# Ground_Station_Board.net
KiCad netlist of a schematic drawn in EAGLE
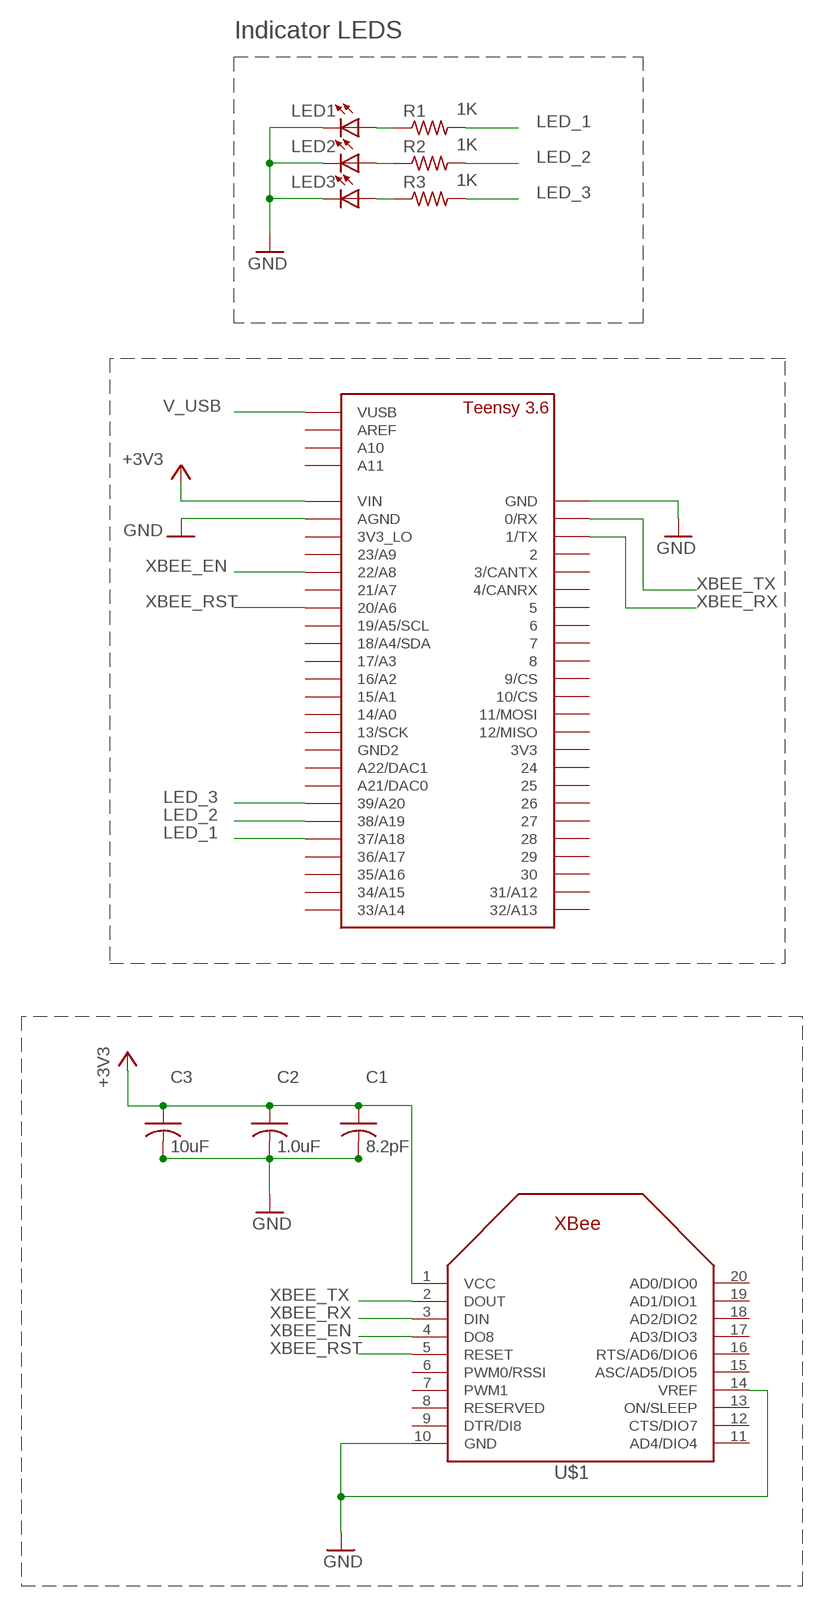
[diagram p0: schematic, sheet 1]

(export (version "E")
  (design (tool "Eeschema 10.0.6"))
  (components
    (comp (ref "C1")
      (value "8.2pF")
      (footprint "eagle-import:C025-024X044")
      (libsource (lib "eagle-import") (part "C-US025-024X044"))
    )
    (comp (ref "C2")
      (value "1.0uF")
      (footprint "eagle-import:C025-024X044")
      (libsource (lib "eagle-import") (part "C-US025-024X044"))
    )
    (comp (ref "C3")
      (value "10uF")
      (footprint "eagle-import:C025-024X044")
      (libsource (lib "eagle-import") (part "C-US025-024X044"))
    )
    (comp (ref "LED1")
      (value "LED5MM")
      (footprint "eagle-import:LED5MM")
      (libsource (lib "eagle-import") (part "LED5MM"))
    )
    (comp (ref "LED2")
      (value "LED5MM")
      (footprint "eagle-import:LED5MM")
      (libsource (lib "eagle-import") (part "LED5MM"))
    )
    (comp (ref "LED3")
      (value "LED5MM")
      (footprint "eagle-import:LED5MM")
      (libsource (lib "eagle-import") (part "LED5MM"))
    )
    (comp (ref "R1")
      (value "1K")
      (footprint "eagle-import:0207_7")
      (libsource (lib "eagle-import") (part "R-US_0207/7"))
    )
    (comp (ref "R2")
      (value "1K")
      (footprint "eagle-import:0207_7")
      (libsource (lib "eagle-import") (part "R-US_0207/7"))
    )
    (comp (ref "R3")
      (value "1K")
      (footprint "eagle-import:0207_7")
      (libsource (lib "eagle-import") (part "R-US_0207/7"))
    )
    (comp (ref "U$1")
      (value "XBEE")
      (footprint "eagle-import:XBEE")
      (libsource (lib "eagle-import") (part "XBEE"))
    )
    (comp (ref "U$2")
      (value "TEENSY_3.5/3.6_BASIC")
      (footprint "eagle-import:TEENSY_3.5_3.6_BASIC")
      (libsource (lib "eagle-import") (part "TEENSY_3.5/3.6_BASIC"))
    )
  )
  (nets
    (net (code "1") (name "+3V3") (class "Default")
      (node (ref "C1") (pin "1") (pinfunction "1_1") (pintype "passive"))
      (node (ref "C2") (pin "1") (pinfunction "1_1") (pintype "passive"))
      (node (ref "C3") (pin "1") (pinfunction "1_1") (pintype "passive"))
      (node (ref "U$1") (pin "1") (pinfunction "VCC_1") (pintype "power_in"))
      (node (ref "U$2") (pin "VIN") (pinfunction "VIN_VIN") (pintype "bidirectional"))
    )
    (net (code "2") (name "/LED_1") (class "Default")
      (node (ref "R1") (pin "2") (pinfunction "2_2") (pintype "passive"))
      (node (ref "U$2") (pin "37/A18") (pinfunction "37/A18_37/A18") (pintype "bidirectional"))
    )
    (net (code "3") (name "/LED_2") (class "Default")
      (node (ref "R2") (pin "2") (pinfunction "2_2") (pintype "passive"))
      (node (ref "U$2") (pin "38/A19") (pinfunction "38/A19_38/A19") (pintype "bidirectional"))
    )
    (net (code "4") (name "/LED_3") (class "Default")
      (node (ref "R3") (pin "2") (pinfunction "2_2") (pintype "passive"))
      (node (ref "U$2") (pin "39/A20") (pinfunction "39/A20_39/A20") (pintype "bidirectional"))
    )
    (net (code "5") (name "/V_USB") (class "Default")
      (node (ref "U$2") (pin "VUSB") (pinfunction "VUSB_VUSB") (pintype "bidirectional"))
    )
    (net (code "6") (name "/XBEE_EN") (class "Default")
      (node (ref "U$1") (pin "4") (pinfunction "DO8_4") (pintype "output"))
      (node (ref "U$2") (pin "22/A8") (pinfunction "22/A8_22/A8") (pintype "bidirectional"))
    )
    (net (code "7") (name "/XBEE_RST") (class "Default")
      (node (ref "U$1") (pin "5") (pinfunction "RESET_5") (pintype "input"))
      (node (ref "U$2") (pin "20/A6") (pinfunction "20/A6_20/A6") (pintype "bidirectional"))
    )
    (net (code "8") (name "/XBEE_RX") (class "Default")
      (node (ref "U$1") (pin "3") (pinfunction "DIN_3") (pintype "input"))
      (node (ref "U$2") (pin "1/TX") (pinfunction "1/TX_1/TX") (pintype "bidirectional"))
    )
    (net (code "9") (name "/XBEE_TX") (class "Default")
      (node (ref "U$1") (pin "2") (pinfunction "DOUT_2") (pintype "output"))
      (node (ref "U$2") (pin "0/RX") (pinfunction "0/RX_0/RX") (pintype "bidirectional"))
    )
    (net (code "10") (name "GND") (class "Default")
      (node (ref "C1") (pin "2") (pinfunction "2_2") (pintype "passive"))
      (node (ref "C2") (pin "2") (pinfunction "2_2") (pintype "passive"))
      (node (ref "C3") (pin "2") (pinfunction "2_2") (pintype "passive"))
      (node (ref "LED1") (pin "K") (pinfunction "C_K") (pintype "passive"))
      (node (ref "LED2") (pin "K") (pinfunction "C_K") (pintype "passive"))
      (node (ref "LED3") (pin "K") (pinfunction "C_K") (pintype "passive"))
      (node (ref "U$1") (pin "10") (pinfunction "GND_10") (pintype "power_in"))
      (node (ref "U$1") (pin "14") (pinfunction "VREF_14") (pintype "input"))
      (node (ref "U$2") (pin "AGND") (pinfunction "AGND_AGND") (pintype "bidirectional"))
      (node (ref "U$2") (pin "GND") (pinfunction "GND_GND") (pintype "bidirectional"))
    )
    (net (code "11") (name "Net-(LED1-PadA)") (class "Default")
      (node (ref "LED1") (pin "A") (pinfunction "A_A") (pintype "passive"))
      (node (ref "R1") (pin "1") (pinfunction "1_1") (pintype "passive"))
    )
    (net (code "12") (name "Net-(LED2-PadA)") (class "Default")
      (node (ref "LED2") (pin "A") (pinfunction "A_A") (pintype "passive"))
      (node (ref "R2") (pin "1") (pinfunction "1_1") (pintype "passive"))
    )
    (net (code "13") (name "Net-(LED3-PadA)") (class "Default")
      (node (ref "LED3") (pin "A") (pinfunction "A_A") (pintype "passive"))
      (node (ref "R3") (pin "1") (pinfunction "1_1") (pintype "passive"))
    )
    (net (code "14") (name "unconnected-(U$1-AD0{slash}DIO0-Pad20)") (class "Default")
      (node (ref "U$1") (pin "20") (pinfunction "AD0/DIO0_20") (pintype "bidirectional"))
    )
    (net (code "15") (name "unconnected-(U$1-AD1{slash}DIO1-Pad19)") (class "Default")
      (node (ref "U$1") (pin "19") (pinfunction "AD1/DIO1_19") (pintype "bidirectional"))
    )
    (net (code "16") (name "unconnected-(U$1-AD2{slash}DIO2-Pad18)") (class "Default")
      (node (ref "U$1") (pin "18") (pinfunction "AD2/DIO2_18") (pintype "bidirectional"))
    )
    (net (code "17") (name "unconnected-(U$1-AD3{slash}DIO3-Pad17)") (class "Default")
      (node (ref "U$1") (pin "17") (pinfunction "AD3/DIO3_17") (pintype "bidirectional"))
    )
    (net (code "18") (name "unconnected-(U$1-AD4{slash}DIO4-Pad11)") (class "Default")
      (node (ref "U$1") (pin "11") (pinfunction "AD4/DIO4_11") (pintype "bidirectional"))
    )
    (net (code "19") (name "unconnected-(U$1-ASC{slash}AD5{slash}DIO5-Pad15)") (class "Default")
      (node (ref "U$1") (pin "15") (pinfunction "ASC/AD5/DIO5_15") (pintype "bidirectional"))
    )
    (net (code "20") (name "unconnected-(U$1-CTS{slash}DIO7-Pad12)") (class "Default")
      (node (ref "U$1") (pin "12") (pinfunction "CTS/DIO7_12") (pintype "bidirectional"))
    )
    (net (code "21") (name "unconnected-(U$1-DTR{slash}DI8-Pad9)") (class "Default")
      (node (ref "U$1") (pin "9") (pinfunction "DTR/DI8_9") (pintype "input"))
    )
    (net (code "22") (name "unconnected-(U$1-ON{slash}SLEEP-Pad13)") (class "Default")
      (node (ref "U$1") (pin "13") (pinfunction "ON/SLEEP_13") (pintype "output"))
    )
    (net (code "23") (name "unconnected-(U$1-PWM0{slash}RSSI-Pad6)") (class "Default")
      (node (ref "U$1") (pin "6") (pinfunction "PWM0/RSSI_6") (pintype "output"))
    )
    (net (code "24") (name "unconnected-(U$1-PWM1-Pad7)") (class "Default")
      (node (ref "U$1") (pin "7") (pinfunction "PWM1_7") (pintype "output"))
    )
    (net (code "25") (name "unconnected-(U$1-RESERVED-Pad8)") (class "Default")
      (node (ref "U$1") (pin "8") (pinfunction "RESERVED_8") (pintype "no_connect"))
    )
    (net (code "26") (name "unconnected-(U$1-RTS{slash}AD6{slash}DIO6-Pad16)") (class "Default")
      (node (ref "U$1") (pin "16") (pinfunction "RTS/AD6/DIO6_16") (pintype "bidirectional"))
    )
    (net (code "27") (name "unconnected-(U$2-A21{slash}DAC0-Pad21{slash}DAC0)") (class "Default")
      (node (ref "U$2") (pin "21/DAC0") (pinfunction "A21/DAC0_21/DAC0") (pintype "bidirectional"))
    )
    (net (code "28") (name "unconnected-(U$2-Pad2)") (class "Default")
      (node (ref "U$2") (pin "2") (pinfunction "2_2") (pintype "bidirectional"))
    )
    (net (code "29") (name "unconnected-(U$2-Pad3V3)") (class "Default")
      (node (ref "U$2") (pin "3V3") (pinfunction "3V3_3V3") (pintype "bidirectional"))
    )
    (net (code "30") (name "unconnected-(U$2-Pad3V3_LO)") (class "Default")
      (node (ref "U$2") (pin "3V3_LO") (pinfunction "3V3_LO_3V3_LO") (pintype "bidirectional"))
    )
    (net (code "31") (name "unconnected-(U$2-Pad3{slash}CANTX)") (class "Default")
      (node (ref "U$2") (pin "3/CANTX") (pinfunction "3/CANTX_3/CANTX") (pintype "bidirectional"))
    )
    (net (code "32") (name "unconnected-(U$2-Pad4{slash}CANRX)") (class "Default")
      (node (ref "U$2") (pin "4/CANRX") (pinfunction "4/CANRX_4/CANRX") (pintype "bidirectional"))
    )
    (net (code "33") (name "unconnected-(U$2-Pad5)") (class "Default")
      (node (ref "U$2") (pin "5") (pinfunction "5_5") (pintype "bidirectional"))
    )
    (net (code "34") (name "unconnected-(U$2-Pad6)") (class "Default")
      (node (ref "U$2") (pin "6") (pinfunction "6_6") (pintype "bidirectional"))
    )
    (net (code "35") (name "unconnected-(U$2-Pad7)") (class "Default")
      (node (ref "U$2") (pin "7") (pinfunction "7_7") (pintype "bidirectional"))
    )
    (net (code "36") (name "unconnected-(U$2-Pad8)") (class "Default")
      (node (ref "U$2") (pin "8") (pinfunction "8_8") (pintype "bidirectional"))
    )
    (net (code "37") (name "unconnected-(U$2-Pad9{slash}CS)") (class "Default")
      (node (ref "U$2") (pin "9/CS") (pinfunction "9/CS_9/CS") (pintype "bidirectional"))
    )
    (net (code "38") (name "unconnected-(U$2-Pad10{slash}CS)") (class "Default")
      (node (ref "U$2") (pin "10/CS") (pinfunction "10/CS_10/CS") (pintype "bidirectional"))
    )
    (net (code "39") (name "unconnected-(U$2-Pad11{slash}MOSI)") (class "Default")
      (node (ref "U$2") (pin "11/MOSI") (pinfunction "11/MOSI_11/MOSI") (pintype "bidirectional"))
    )
    (net (code "40") (name "unconnected-(U$2-Pad12{slash}MISO)") (class "Default")
      (node (ref "U$2") (pin "12/MISO") (pinfunction "12/MISO_12/MISO") (pintype "bidirectional"))
    )
    (net (code "41") (name "unconnected-(U$2-Pad13{slash}SCK)") (class "Default")
      (node (ref "U$2") (pin "13/SCK") (pinfunction "13/SCK_13/SCK") (pintype "bidirectional"))
    )
    (net (code "42") (name "unconnected-(U$2-Pad14{slash}A0)") (class "Default")
      (node (ref "U$2") (pin "14/A0") (pinfunction "14/A0_14/A0") (pintype "bidirectional"))
    )
    (net (code "43") (name "unconnected-(U$2-Pad15{slash}A1)") (class "Default")
      (node (ref "U$2") (pin "15/A1") (pinfunction "15/A1_15/A1") (pintype "bidirectional"))
    )
    (net (code "44") (name "unconnected-(U$2-Pad16{slash}A2)") (class "Default")
      (node (ref "U$2") (pin "16/A2") (pinfunction "16/A2_16/A2") (pintype "bidirectional"))
    )
    (net (code "45") (name "unconnected-(U$2-Pad17{slash}A3)") (class "Default")
      (node (ref "U$2") (pin "17/A3") (pinfunction "17/A3_17/A3") (pintype "bidirectional"))
    )
    (net (code "46") (name "unconnected-(U$2-Pad18{slash}A4{slash}SDA)") (class "Default")
      (node (ref "U$2") (pin "18/A4/SDA") (pinfunction "18/A4/SDA_18/A4/SDA") (pintype "bidirectional"))
    )
    (net (code "47") (name "unconnected-(U$2-Pad19{slash}A5{slash}SCL)") (class "Default")
      (node (ref "U$2") (pin "19/A5/SCL") (pinfunction "19/A5/SCL_19/A5/SCL") (pintype "bidirectional"))
    )
    (net (code "48") (name "unconnected-(U$2-Pad21{slash}A7)") (class "Default")
      (node (ref "U$2") (pin "21/A7") (pinfunction "21/A7_21/A7") (pintype "bidirectional"))
    )
    (net (code "49") (name "unconnected-(U$2-Pad23{slash}A9)") (class "Default")
      (node (ref "U$2") (pin "23/A9") (pinfunction "23/A9_23/A9") (pintype "bidirectional"))
    )
    (net (code "50") (name "unconnected-(U$2-Pad24)") (class "Default")
      (node (ref "U$2") (pin "24") (pinfunction "24_24") (pintype "bidirectional"))
    )
    (net (code "51") (name "unconnected-(U$2-Pad25)") (class "Default")
      (node (ref "U$2") (pin "25") (pinfunction "25_25") (pintype "bidirectional"))
    )
    (net (code "52") (name "unconnected-(U$2-Pad26)") (class "Default")
      (node (ref "U$2") (pin "26") (pinfunction "26_26") (pintype "bidirectional"))
    )
    (net (code "53") (name "unconnected-(U$2-Pad27)") (class "Default")
      (node (ref "U$2") (pin "27") (pinfunction "27_27") (pintype "bidirectional"))
    )
    (net (code "54") (name "unconnected-(U$2-Pad28)") (class "Default")
      (node (ref "U$2") (pin "28") (pinfunction "28_28") (pintype "bidirectional"))
    )
    (net (code "55") (name "unconnected-(U$2-Pad29)") (class "Default")
      (node (ref "U$2") (pin "29") (pinfunction "29_29") (pintype "bidirectional"))
    )
    (net (code "56") (name "unconnected-(U$2-Pad30)") (class "Default")
      (node (ref "U$2") (pin "30") (pinfunction "30_30") (pintype "bidirectional"))
    )
    (net (code "57") (name "unconnected-(U$2-Pad31{slash}A12)") (class "Default")
      (node (ref "U$2") (pin "31/A12") (pinfunction "31/A12_31/A12") (pintype "bidirectional"))
    )
    (net (code "58") (name "unconnected-(U$2-Pad32{slash}A13)") (class "Default")
      (node (ref "U$2") (pin "32/A13") (pinfunction "32/A13_32/A13") (pintype "bidirectional"))
    )
    (net (code "59") (name "unconnected-(U$2-Pad33{slash}A14)") (class "Default")
      (node (ref "U$2") (pin "33/A14") (pinfunction "33/A14_33/A14") (pintype "bidirectional"))
    )
    (net (code "60") (name "unconnected-(U$2-Pad34{slash}A15)") (class "Default")
      (node (ref "U$2") (pin "34/A15") (pinfunction "34/A15_34/A15") (pintype "bidirectional"))
    )
    (net (code "61") (name "unconnected-(U$2-Pad35{slash}A16)") (class "Default")
      (node (ref "U$2") (pin "35/A16") (pinfunction "35/A16_35/A16") (pintype "bidirectional"))
    )
    (net (code "62") (name "unconnected-(U$2-Pad36{slash}A17)") (class "Default")
      (node (ref "U$2") (pin "36/A17") (pinfunction "36/A17_36/A17") (pintype "bidirectional"))
    )
    (net (code "63") (name "unconnected-(U$2-PadA10)") (class "Default")
      (node (ref "U$2") (pin "A10") (pinfunction "A10_A10") (pintype "bidirectional"))
    )
    (net (code "64") (name "unconnected-(U$2-PadA11)") (class "Default")
      (node (ref "U$2") (pin "A11") (pinfunction "A11_A11") (pintype "bidirectional"))
    )
    (net (code "65") (name "unconnected-(U$2-PadA22{slash}DAC1)") (class "Default")
      (node (ref "U$2") (pin "A22/DAC1") (pinfunction "A22/DAC1_A22/DAC1") (pintype "bidirectional"))
    )
    (net (code "66") (name "unconnected-(U$2-PadAREF)") (class "Default")
      (node (ref "U$2") (pin "AREF") (pinfunction "AREF_AREF") (pintype "bidirectional"))
    )
    (net (code "67") (name "unconnected-(U$2-PadGND2)") (class "Default")
      (node (ref "U$2") (pin "GND2") (pinfunction "GND2_GND2") (pintype "bidirectional"))
    )
  )
)
